# Microcontroller.net
KiCad netlist of a schematic drawn in Altium Designer
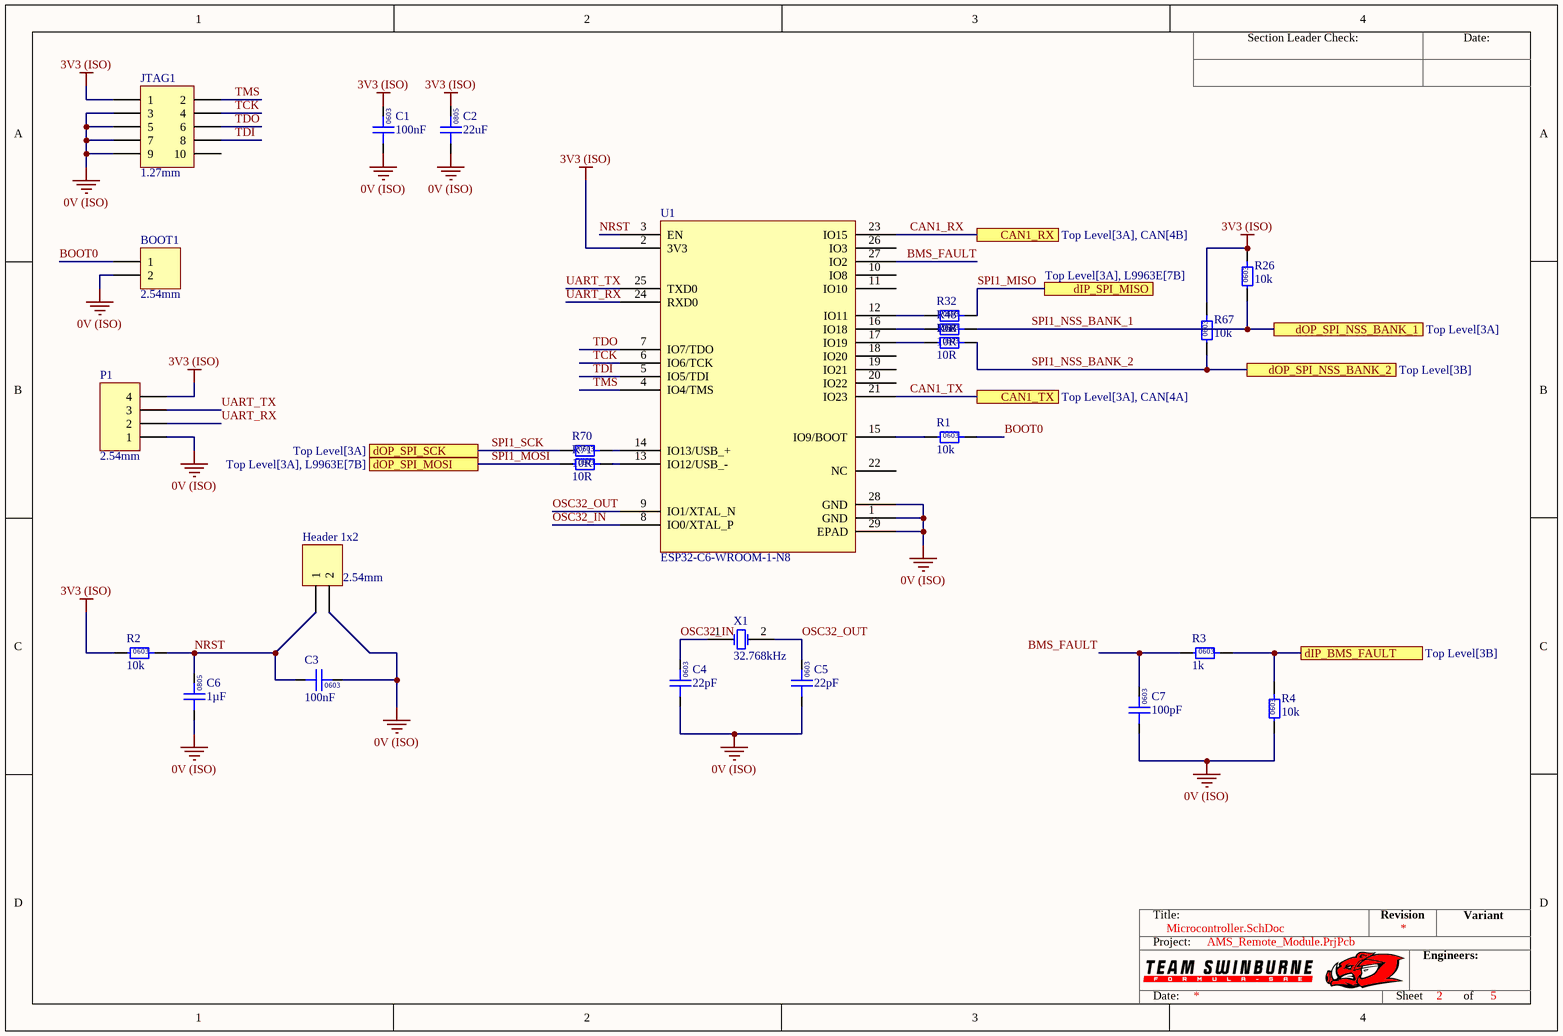
[diagram p0: Microcontroller.SchDoc]

(export (version "E")
  (design (tool "Eeschema 10.0.6"))
  (components
    (comp (ref "BOOT1")
      (value "2.54mm")
      (footprint "TH 2.54mm Header 1x2")
      (fields (field (name "PART NUMBER") "TH 2.54mm Header 1x2") (field (name "CONTACT") "NA"))
      (libsource (lib "") (part "Header 1x2_1"))
    )
    (comp (ref "C1")
      (value "100nF")
      (footprint "0603")
      (fields
        (field (name "PART NUMBER") "GCM188L81H104KA57D")
        (field (name "MANUFACTURER") "muRata")
        (field (name "TOLERANCE") "±10%")
      )
      (libsource (lib "ts_standard_library") (part "Capacitor 0603"))
    )
    (comp (ref "C2")
      (value "22uF")
      (footprint "0805")
      (fields
        (field (name "PART NUMBER") "GRM21BR61A226ME51L")
        (field (name "MANUFACTURER") "muRata")
        (field (name "TOLERANCE") "20%")
      )
      (libsource (lib "ts_standard_library") (part "Capacitor 0805"))
    )
    (comp (ref "C3")
      (value "100nF")
      (footprint "0603")
      (fields
        (field (name "PART NUMBER") "GCM188L81H104KA57D")
        (field (name "MANUFACTURER") "muRata")
        (field (name "TOLERANCE") "±10%")
      )
      (libsource (lib "ts_standard_library") (part "Capacitor 0603"))
    )
    (comp (ref "C4")
      (value "22pF")
      (footprint "0603")
      (fields
        (field (name "PART NUMBER") "GRM0335C1H220JA01D")
        (field (name "MANUFACTURER") "Murata Electronics")
        (field (name "TOLERANCE") "±5%")
      )
      (libsource (lib "ts_standard_library") (part "Capacitor 0603"))
    )
    (comp (ref "C5")
      (value "22pF")
      (footprint "0603")
      (fields
        (field (name "PART NUMBER") "GRM0335C1H220JA01D")
        (field (name "MANUFACTURER") "Murata Electronics")
        (field (name "TOLERANCE") "±5%")
      )
      (libsource (lib "ts_standard_library") (part "Capacitor 0603"))
    )
    (comp (ref "C6")
      (value "1µF")
      (footprint "0805")
      (fields
        (field (name "PART NUMBER") "GCM21BR71H105KA03L")
        (field (name "MANUFACTURER") "muRata")
        (field (name "TOLERANCE") "±10%")
      )
      (libsource (lib "ts_standard_library") (part "Capacitor 0805"))
    )
    (comp (ref "C7")
      (value "100pF")
      (footprint "0603")
      (fields
        (field (name "PART NUMBER") "GRM1885C1H101JA01D")
        (field (name "MANUFACTURER") "Murata Electronics")
        (field (name "TOLERANCE") "±5%")
      )
      (libsource (lib "ts_standard_library") (part "Capacitor 0603"))
    )
    (comp (ref "Header 1x2")
      (value "2.54mm")
      (footprint "TH 2.54mm Header 1x2")
      (fields (field (name "PART NUMBER") "TH 2.54mm Header 1x2") (field (name "CONTACT") "NA"))
      (libsource (lib "ts_standard_connectors") (part "Header 1x2"))
    )
    (comp (ref "JTAG1")
      (value "1.27mm")
      (footprint "3221-10-0300-00")
      (fields
        (field (name "PART NUMBER") "SMD 1.27mm Header 2x5 (3221-10-0300-00)")
        (field (name "CONTACT") "NA")
      )
      (libsource (lib "ts_standard_connectors") (part "Header 2x5"))
    )
    (comp (ref "P1")
      (value "2.54mm")
      (footprint "TH 2.54mm Header 1x4")
      (fields (field (name "PART NUMBER") "TH 2.54mm Header 1x4") (field (name "CONTACT") "NA"))
      (libsource (lib "ts_standard_connectors") (part "Header 1x4"))
    )
    (comp (ref "R1")
      (value "10k")
      (footprint "0603")
      (fields
        (field (name "PART NUMBER") "RC0603FR-0710KL")
        (field (name "MANUFACTURER") "YAGEO")
        (field (name "TOLERANCE") "0.01")
      )
      (libsource (lib "ts_standard_library") (part "Resistor 0603"))
    )
    (comp (ref "R2")
      (value "10k")
      (footprint "0603")
      (fields
        (field (name "PART NUMBER") "RC0603FR-0710KL")
        (field (name "MANUFACTURER") "YAGEO")
        (field (name "TOLERANCE") "0.01")
      )
      (libsource (lib "ts_standard_library") (part "Resistor 0603"))
    )
    (comp (ref "R3")
      (value "1k")
      (footprint "0603")
      (fields
        (field (name "PART NUMBER") "RC0603FR-071KL")
        (field (name "MANUFACTURER") "YAGEO")
        (field (name "TOLERANCE") "0.01")
      )
      (libsource (lib "ts_standard_library") (part "Resistor 0603"))
    )
    (comp (ref "R4")
      (value "10k")
      (footprint "0603")
      (fields
        (field (name "PART NUMBER") "RC0603FR-0710KL")
        (field (name "MANUFACTURER") "YAGEO")
        (field (name "TOLERANCE") "0.01")
      )
      (libsource (lib "ts_standard_library") (part "Resistor 0603"))
    )
    (comp (ref "R26")
      (value "10k")
      (footprint "0603")
      (fields
        (field (name "PART NUMBER") "RC0603FR-0710KL")
        (field (name "MANUFACTURER") "YAGEO")
        (field (name "TOLERANCE") "0.01")
      )
      (libsource (lib "ts_standard_library") (part "Resistor 0603"))
    )
    (comp (ref "R32")
      (value "10R")
      (footprint "0603")
      (fields
        (field (name "PART NUMBER") "RC0603FR-0710RL")
        (field (name "MANUFACTURER") "YAGEO")
        (field (name "TOLERANCE") "0.01")
      )
      (libsource (lib "ts_standard_library") (part "Resistor 0603"))
    )
    (comp (ref "R48")
      (value "10R")
      (footprint "0603")
      (fields
        (field (name "PART NUMBER") "RC0603FR-0710RL")
        (field (name "MANUFACTURER") "YAGEO")
        (field (name "TOLERANCE") "0.01")
      )
      (libsource (lib "ts_standard_library") (part "Resistor 0603"))
    )
    (comp (ref "R67")
      (value "10k")
      (footprint "0603")
      (fields
        (field (name "PART NUMBER") "RC0603FR-0710KL")
        (field (name "MANUFACTURER") "YAGEO")
        (field (name "TOLERANCE") "0.01")
      )
      (libsource (lib "ts_standard_library") (part "Resistor 0603"))
    )
    (comp (ref "R68")
      (value "10R")
      (footprint "0603")
      (fields
        (field (name "PART NUMBER") "RC0603FR-0710RL")
        (field (name "MANUFACTURER") "YAGEO")
        (field (name "TOLERANCE") "0.01")
      )
      (libsource (lib "ts_standard_library") (part "Resistor 0603"))
    )
    (comp (ref "R70")
      (value "10R")
      (footprint "0603")
      (fields
        (field (name "PART NUMBER") "RC0603FR-0710RL")
        (field (name "MANUFACTURER") "YAGEO")
        (field (name "TOLERANCE") "0.01")
      )
      (libsource (lib "ts_standard_library") (part "Resistor 0603"))
    )
    (comp (ref "R71")
      (value "10R")
      (footprint "0603")
      (fields
        (field (name "PART NUMBER") "RC0603FR-0710RL")
        (field (name "MANUFACTURER") "YAGEO")
        (field (name "TOLERANCE") "0.01")
      )
      (libsource (lib "ts_standard_library") (part "Resistor 0603"))
    )
    (comp (ref "U1")
      (value "ESP32-C6-WROOM-1-N8")
      (footprint "ESP32-C6-WROOM-1-N8")
      (description "RF TXRX MOD BT WIFI PCB TH SMD")
      (fields (field (name "MANUFACTURER") "Espressif"))
      (libsource (lib "ts_standard_library") (part "ESP32-C6-WROOM-1-N8"))
    )
    (comp (ref "X1")
      (value "32.768kHz")
      (footprint "EPSON 2-SMD")
      (fields
        (field (name "PART NUMBER") "FC-135 32.7680KA-A5")
        (field (name "MANUFACTURER") "EPSON")
        (field (name "DIGIKEY PART NUMBER") "SER4103TR-ND")
      )
      (libsource (lib "ts_standard_library") (part "Crystal"))
    )
  )
  (nets
    (net (code "1") (name "/BMS_FAULT") (class "Default")
      (node (ref "C7") (pin "2") (pinfunction "2_2") (pintype "passive"))
      (node (ref "R3") (pin "1") (pinfunction "1_1") (pintype "passive"))
      (node (ref "U1") (pin "27") (pinfunction "IO2_27") (pintype "passive"))
    )
    (net (code "2") (name "/BOOT0") (class "Default")
      (node (ref "BOOT1") (pin "1") (pinfunction "1_1") (pintype "passive"))
      (node (ref "R1") (pin "2") (pinfunction "2_2") (pintype "passive"))
    )
    (net (code "3") (name "/CAN1_RX") (class "Default")
      (node (ref "U1") (pin "23") (pinfunction "IO15_23") (pintype "passive"))
    )
    (net (code "4") (name "/CAN1_TX") (class "Default")
      (node (ref "U1") (pin "21") (pinfunction "IO23_21") (pintype "passive"))
    )
    (net (code "5") (name "/NRST") (class "Default")
      (node (ref "C3") (pin "1") (pinfunction "1_1") (pintype "passive"))
      (node (ref "C6") (pin "2") (pinfunction "2_2") (pintype "passive"))
      (node (ref "Header 1x2") (pin "1") (pinfunction "1_1") (pintype "passive"))
      (node (ref "R2") (pin "2") (pinfunction "2_2") (pintype "passive"))
      (node (ref "U1") (pin "3") (pinfunction "EN_3") (pintype "passive"))
    )
    (net (code "6") (name "/OSC32_IN") (class "Default")
      (node (ref "C4") (pin "2") (pinfunction "2_2") (pintype "passive"))
      (node (ref "U1") (pin "8") (pinfunction "IO0/XTAL_P_8") (pintype "passive"))
      (node (ref "X1") (pin "1") (pinfunction "OSC1_1") (pintype "passive"))
    )
    (net (code "7") (name "/OSC32_OUT") (class "Default")
      (node (ref "C5") (pin "2") (pinfunction "2_2") (pintype "passive"))
      (node (ref "U1") (pin "9") (pinfunction "IO1/XTAL_N_9") (pintype "passive"))
      (node (ref "X1") (pin "2") (pinfunction "OSC2_2") (pintype "passive"))
    )
    (net (code "8") (name "/SPI1_MISO") (class "Default")
      (node (ref "R32") (pin "2") (pinfunction "2_2") (pintype "passive"))
    )
    (net (code "9") (name "/SPI1_MOSI") (class "Default")
      (node (ref "R71") (pin "1") (pinfunction "1_1") (pintype "passive"))
    )
    (net (code "10") (name "/SPI1_NSS_BANK_1") (class "Default")
      (node (ref "R26") (pin "1") (pinfunction "1_1") (pintype "passive"))
      (node (ref "R48") (pin "2") (pinfunction "2_2") (pintype "passive"))
    )
    (net (code "11") (name "/SPI1_NSS_BANK_2") (class "Default")
      (node (ref "R67") (pin "1") (pinfunction "1_1") (pintype "passive"))
      (node (ref "R68") (pin "2") (pinfunction "2_2") (pintype "passive"))
    )
    (net (code "12") (name "/SPI1_SCK") (class "Default")
      (node (ref "R70") (pin "1") (pinfunction "1_1") (pintype "passive"))
    )
    (net (code "13") (name "/TCK") (class "Default")
      (node (ref "JTAG1") (pin "4") (pinfunction "4_4") (pintype "passive"))
      (node (ref "U1") (pin "6") (pinfunction "IO6/TCK_6") (pintype "passive"))
    )
    (net (code "14") (name "/TDI") (class "Default")
      (node (ref "JTAG1") (pin "8") (pinfunction "8_8") (pintype "passive"))
      (node (ref "U1") (pin "5") (pinfunction "IO5/TDI_5") (pintype "passive"))
    )
    (net (code "15") (name "/TDO") (class "Default")
      (node (ref "JTAG1") (pin "6") (pinfunction "6_6") (pintype "passive"))
      (node (ref "U1") (pin "7") (pinfunction "IO7/TDO_7") (pintype "passive"))
    )
    (net (code "16") (name "/TMS") (class "Default")
      (node (ref "JTAG1") (pin "2") (pinfunction "2_2") (pintype "passive"))
      (node (ref "U1") (pin "4") (pinfunction "IO4/TMS_4") (pintype "passive"))
    )
    (net (code "17") (name "/UART_RX") (class "Default")
      (node (ref "P1") (pin "2") (pinfunction "2_2") (pintype "passive"))
      (node (ref "U1") (pin "24") (pinfunction "RXD0_24") (pintype "passive"))
    )
    (net (code "18") (name "/UART_TX") (class "Default")
      (node (ref "P1") (pin "3") (pinfunction "3_3") (pintype "passive"))
      (node (ref "U1") (pin "25") (pinfunction "TXD0_25") (pintype "passive"))
    )
    (net (code "19") (name "/dIP_BMS_FAULT") (class "Default")
      (node (ref "R3") (pin "2") (pinfunction "2_2") (pintype "passive"))
      (node (ref "R4") (pin "2") (pinfunction "2_2") (pintype "passive"))
    )
    (net (code "20") (name "0V (ISO)") (class "Default")
      (node (ref "BOOT1") (pin "2") (pinfunction "2_2") (pintype "passive"))
      (node (ref "C1") (pin "1") (pinfunction "1_1") (pintype "passive"))
      (node (ref "C2") (pin "1") (pinfunction "1_1") (pintype "passive"))
      (node (ref "C3") (pin "2") (pinfunction "2_2") (pintype "passive"))
      (node (ref "C4") (pin "1") (pinfunction "1_1") (pintype "passive"))
      (node (ref "C5") (pin "1") (pinfunction "1_1") (pintype "passive"))
      (node (ref "C6") (pin "1") (pinfunction "1_1") (pintype "passive"))
      (node (ref "C7") (pin "1") (pinfunction "1_1") (pintype "passive"))
      (node (ref "Header 1x2") (pin "2") (pinfunction "2_2") (pintype "passive"))
      (node (ref "JTAG1") (pin "3") (pinfunction "3_3") (pintype "passive"))
      (node (ref "JTAG1") (pin "5") (pinfunction "5_5") (pintype "passive"))
      (node (ref "JTAG1") (pin "7") (pinfunction "7_7") (pintype "passive"))
      (node (ref "JTAG1") (pin "9") (pinfunction "9_9") (pintype "passive"))
      (node (ref "P1") (pin "1") (pinfunction "1_1") (pintype "passive"))
      (node (ref "R4") (pin "1") (pinfunction "1_1") (pintype "passive"))
      (node (ref "U1") (pin "1") (pinfunction "GND_1") (pintype "passive"))
      (node (ref "U1") (pin "28") (pinfunction "GND_28") (pintype "passive"))
      (node (ref "U1") (pin "29") (pinfunction "EPAD_29") (pintype "passive"))
    )
    (net (code "21") (name "3V3 (ISO)") (class "Default")
      (node (ref "C1") (pin "2") (pinfunction "2_2") (pintype "passive"))
      (node (ref "C2") (pin "2") (pinfunction "2_2") (pintype "passive"))
      (node (ref "JTAG1") (pin "1") (pinfunction "1_1") (pintype "passive"))
      (node (ref "P1") (pin "4") (pinfunction "4_4") (pintype "passive"))
      (node (ref "R2") (pin "1") (pinfunction "1_1") (pintype "passive"))
      (node (ref "R26") (pin "2") (pinfunction "2_2") (pintype "passive"))
      (node (ref "R67") (pin "2") (pinfunction "2_2") (pintype "passive"))
      (node (ref "U1") (pin "2") (pinfunction "3V3_2") (pintype "passive"))
    )
    (net (code "22") (name "Net-(U1-IO9{slash}BOOT)") (class "Default")
      (node (ref "R1") (pin "1") (pinfunction "1_1") (pintype "passive"))
      (node (ref "U1") (pin "15") (pinfunction "IO9/BOOT_15") (pintype "passive"))
    )
    (net (code "23") (name "Net-(U1-IO11)") (class "Default")
      (node (ref "R32") (pin "1") (pinfunction "1_1") (pintype "passive"))
      (node (ref "U1") (pin "12") (pinfunction "IO11_12") (pintype "passive"))
    )
    (net (code "24") (name "Net-(U1-IO12{slash}USB_-)") (class "Default")
      (node (ref "R71") (pin "2") (pinfunction "2_2") (pintype "passive"))
      (node (ref "U1") (pin "13") (pinfunction "IO12/USB_-_13") (pintype "passive"))
    )
    (net (code "25") (name "Net-(U1-IO13{slash}USB_+)") (class "Default")
      (node (ref "R70") (pin "2") (pinfunction "2_2") (pintype "passive"))
      (node (ref "U1") (pin "14") (pinfunction "IO13/USB_+_14") (pintype "passive"))
    )
    (net (code "26") (name "Net-(U1-IO18)") (class "Default")
      (node (ref "R48") (pin "1") (pinfunction "1_1") (pintype "passive"))
      (node (ref "U1") (pin "16") (pinfunction "IO18_16") (pintype "passive"))
    )
    (net (code "27") (name "Net-(U1-IO19)") (class "Default")
      (node (ref "R68") (pin "1") (pinfunction "1_1") (pintype "passive"))
      (node (ref "U1") (pin "17") (pinfunction "IO19_17") (pintype "passive"))
    )
    (net (code "28") (name "unconnected-(JTAG1-Pad10)") (class "Default")
      (node (ref "JTAG1") (pin "10") (pinfunction "10_10") (pintype "passive"))
    )
    (net (code "29") (name "unconnected-(U1-IO3-Pad26)") (class "Default")
      (node (ref "U1") (pin "26") (pinfunction "IO3_26") (pintype "passive"))
    )
    (net (code "30") (name "unconnected-(U1-IO8-Pad10)") (class "Default")
      (node (ref "U1") (pin "10") (pinfunction "IO8_10") (pintype "passive"))
    )
    (net (code "31") (name "unconnected-(U1-IO10-Pad11)") (class "Default")
      (node (ref "U1") (pin "11") (pinfunction "IO10_11") (pintype "passive"))
    )
    (net (code "32") (name "unconnected-(U1-IO20-Pad18)") (class "Default")
      (node (ref "U1") (pin "18") (pinfunction "IO20_18") (pintype "passive"))
    )
    (net (code "33") (name "unconnected-(U1-IO21-Pad19)") (class "Default")
      (node (ref "U1") (pin "19") (pinfunction "IO21_19") (pintype "passive"))
    )
    (net (code "34") (name "unconnected-(U1-IO22-Pad20)") (class "Default")
      (node (ref "U1") (pin "20") (pinfunction "IO22_20") (pintype "passive"))
    )
    (net (code "35") (name "unconnected-(U1-NC-Pad22)") (class "Default")
      (node (ref "U1") (pin "22") (pinfunction "NC_22") (pintype "passive"))
    )
  )
)
